# LIS2DE12TR.net
KiCad netlist of a schematic drawn in Altium Designer
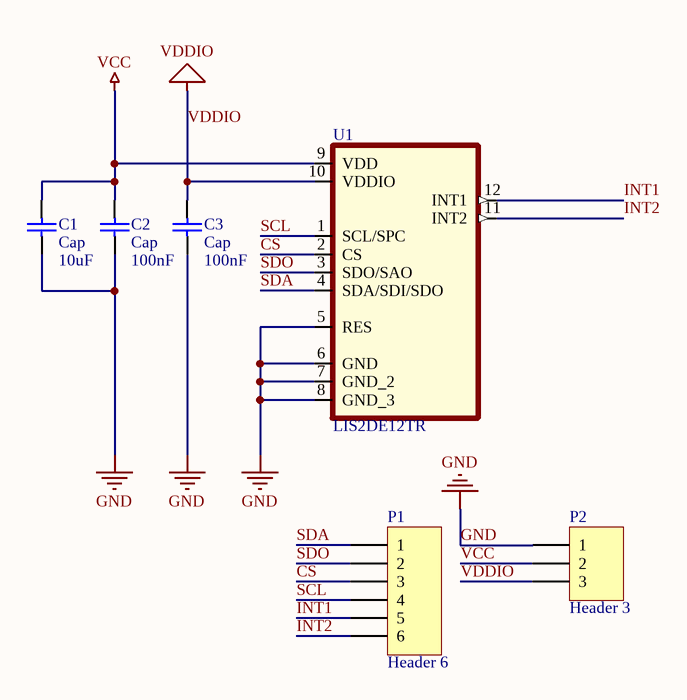
[diagram p0: LIS2DE12TR.SchDoc]

(export (version "E")
  (design (tool "Eeschema 10.0.6"))
  (components
    (comp (ref "C1")
      (value "Cap")
      (footprint "capacitor_10uf")
      (description "Capacitor")
      (fields (field (name "ALTIUM_VALUE") "10uF") (field (name "PUBLISHER") "Altium Limited"))
      (libsource (lib "Miscellaneous Devices") (part "Cap"))
    )
    (comp (ref "C2")
      (value "Cap")
      (footprint "capacitor_10uf")
      (description "Capacitor")
      (fields (field (name "ALTIUM_VALUE") "100nF") (field (name "PUBLISHER") "Altium Limited"))
      (libsource (lib "Miscellaneous Devices") (part "Cap"))
    )
    (comp (ref "C3")
      (value "Cap")
      (footprint "capacitor_10uf")
      (description "Capacitor")
      (fields (field (name "ALTIUM_VALUE") "100nF") (field (name "PUBLISHER") "Altium Limited"))
      (libsource (lib "Miscellaneous Devices") (part "Cap"))
    )
    (comp (ref "P1")
      (value "Header 6")
      (footprint "HDR1X6")
      (description "Header, 6-Pin")
      (fields (field (name "PUBLISHER") "Altium Limited"))
      (libsource (lib "Miscellaneous Connectors") (part "Header 6"))
    )
    (comp (ref "P2")
      (value "Header 3")
      (footprint "HDR1X3")
      (description "Header, 3-Pin")
      (fields (field (name "PUBLISHER") "Altium Limited"))
      (libsource (lib "Miscellaneous Connectors") (part "Header 3"))
    )
    (comp (ref "U1")
      (value "LIS2DE12TR")
      (footprint "LIS2DE12TR")
      (libsource (lib "Accelerometres") (part "LIS2DE12TR"))
    )
  )
  (nets
    (net (code "1") (name "/CS") (class "Default")
      (node (ref "P1") (pin "3") (pinfunction "3_3") (pintype "passive"))
      (node (ref "U1") (pin "2") (pinfunction "CS_2") (pintype "passive"))
    )
    (net (code "2") (name "/INT1") (class "Default")
      (node (ref "P1") (pin "5") (pinfunction "5_5") (pintype "passive"))
      (node (ref "U1") (pin "12") (pinfunction "INT1_12") (pintype "output"))
    )
    (net (code "3") (name "/INT2") (class "Default")
      (node (ref "P1") (pin "6") (pinfunction "6_6") (pintype "passive"))
      (node (ref "U1") (pin "11") (pinfunction "INT2_11") (pintype "output"))
    )
    (net (code "4") (name "/SCL") (class "Default")
      (node (ref "P1") (pin "4") (pinfunction "4_4") (pintype "passive"))
      (node (ref "U1") (pin "1") (pinfunction "SCL/SPC_1") (pintype "passive"))
    )
    (net (code "5") (name "/SDA") (class "Default")
      (node (ref "P1") (pin "1") (pinfunction "1_1") (pintype "passive"))
      (node (ref "U1") (pin "4") (pinfunction "SDA/SDI/SDO_4") (pintype "bidirectional"))
    )
    (net (code "6") (name "/SDO") (class "Default")
      (node (ref "P1") (pin "2") (pinfunction "2_2") (pintype "passive"))
      (node (ref "U1") (pin "3") (pinfunction "SDO/SAO_3") (pintype "bidirectional"))
    )
    (net (code "7") (name "GND") (class "Default")
      (node (ref "C1") (pin "1") (pinfunction "1_1") (pintype "passive"))
      (node (ref "C2") (pin "1") (pinfunction "1_1") (pintype "passive"))
      (node (ref "C3") (pin "1") (pinfunction "1_1") (pintype "passive"))
      (node (ref "P2") (pin "1") (pinfunction "1_1") (pintype "passive"))
      (node (ref "U1") (pin "5") (pinfunction "RES_5") (pintype "passive"))
      (node (ref "U1") (pin "6") (pinfunction "GND_6") (pintype "passive"))
      (node (ref "U1") (pin "7") (pinfunction "GND_2_7") (pintype "passive"))
      (node (ref "U1") (pin "8") (pinfunction "GND_3_8") (pintype "passive"))
    )
    (net (code "8") (name "VCC") (class "Default")
      (node (ref "C1") (pin "2") (pinfunction "2_2") (pintype "passive"))
      (node (ref "C2") (pin "2") (pinfunction "2_2") (pintype "passive"))
      (node (ref "P2") (pin "2") (pinfunction "2_2") (pintype "passive"))
      (node (ref "U1") (pin "9") (pinfunction "VDD_9") (pintype "power_in"))
    )
    (net (code "9") (name "VDDIO") (class "Default")
      (node (ref "C3") (pin "2") (pinfunction "2_2") (pintype "passive"))
      (node (ref "P2") (pin "3") (pinfunction "3_3") (pintype "passive"))
      (node (ref "U1") (pin "10") (pinfunction "VDDIO_10") (pintype "power_in"))
    )
  )
)
